# Led7Seg.net
KiCad netlist of a schematic drawn in Altium Designer
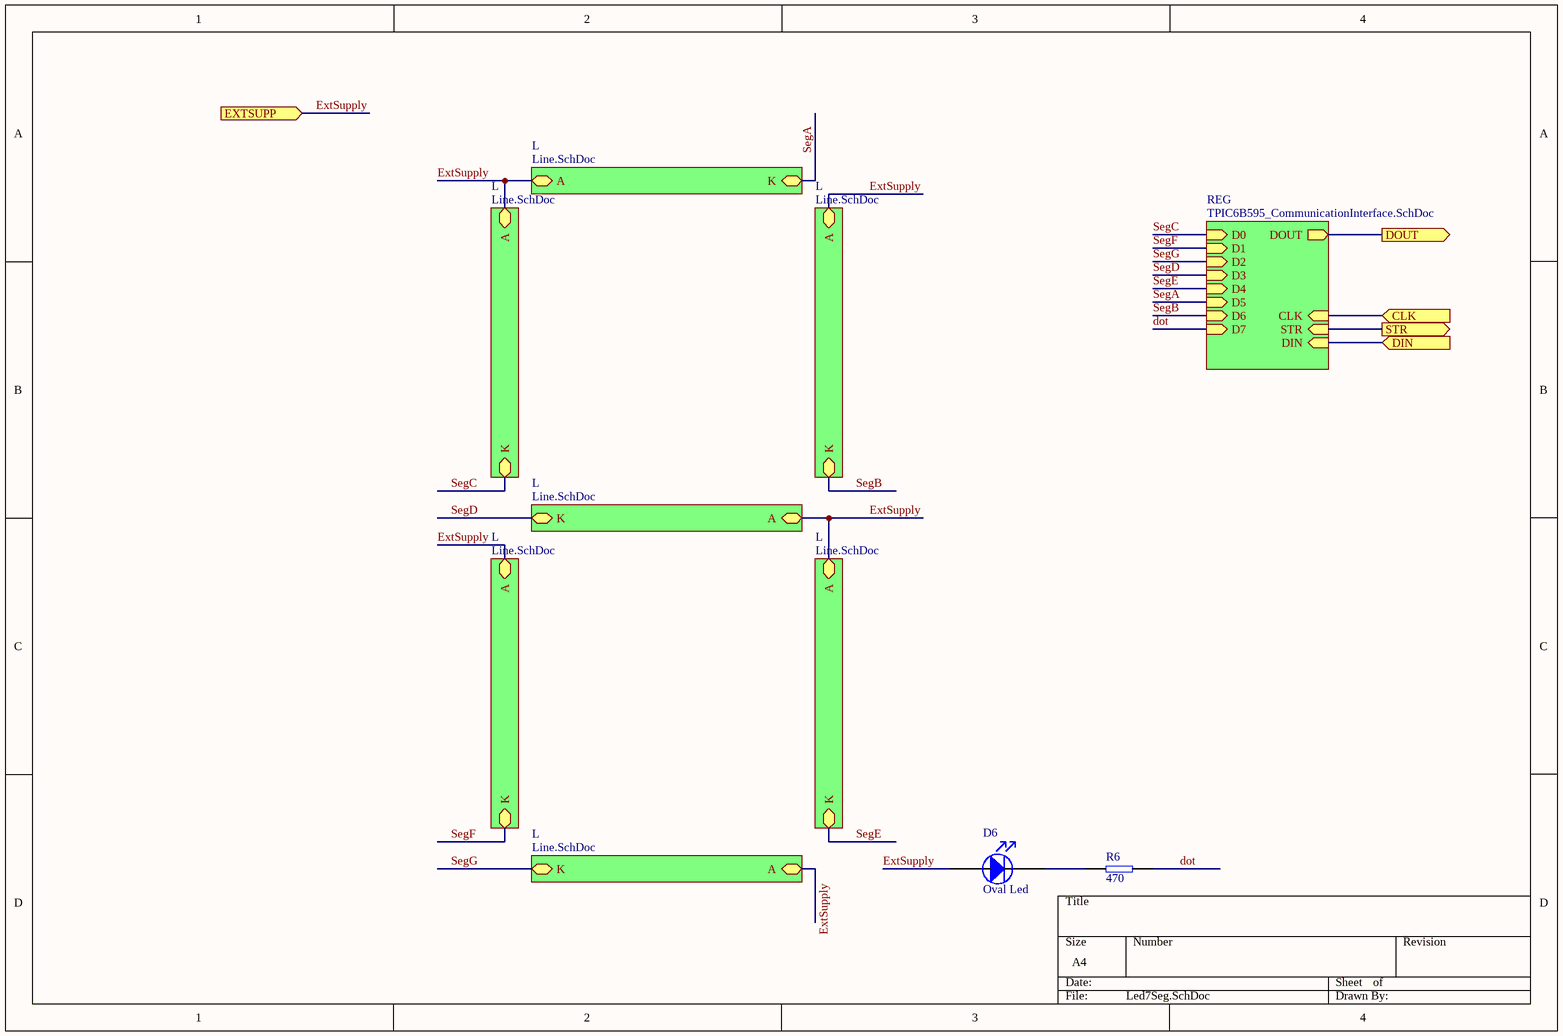
[diagram p0: Led7Seg.SchDoc]

(export (version "E")
  (design (tool "Eeschema 10.0.6"))
  (components
    (comp (ref "D6")
      (value "Oval Led")
      (footprint "LED")
      (description "LED estándar - Montaje interfacial Red Oval LED")
      (fields (field (name "MPN") "C566C-RFN-CV0W0BB2"))
      (libsource (lib "Miscellaneous Devices") (part "Oval Led"))
    )
    (comp (ref "R6")
      (value "470")
      (footprint "RES2512")
      (description "Resistores de película gruesa - SMD 1watt 470ohms 5%")
      (fields (field (name "MPN") "CRCW2512470RJNEG") (field (name "Comment") "RES470"))
      (libsource (lib "Miscellaneous Devices") (part "RES470"))
    )
  )
  (nets
    (net (code "4") (name "/ExtSupply") (class "Default")
      (node (ref "D6") (pin "A") (pinfunction "Anode_A") (pintype "passive"))
    )
    (net (code "13") (name "/dot") (class "Default")
      (node (ref "R6") (pin "2") (pinfunction "neg_2") (pintype "passive"))
    )
    (net (code "14") (name "Net-(D6-Cathode)") (class "Default")
      (node (ref "D6") (pin "K") (pinfunction "Cathode_K") (pintype "passive"))
      (node (ref "R6") (pin "1") (pinfunction "pos_1") (pintype "passive"))
    )
  )
)
